# bttoken.net
KiCad netlist of a schematic drawn in EAGLE
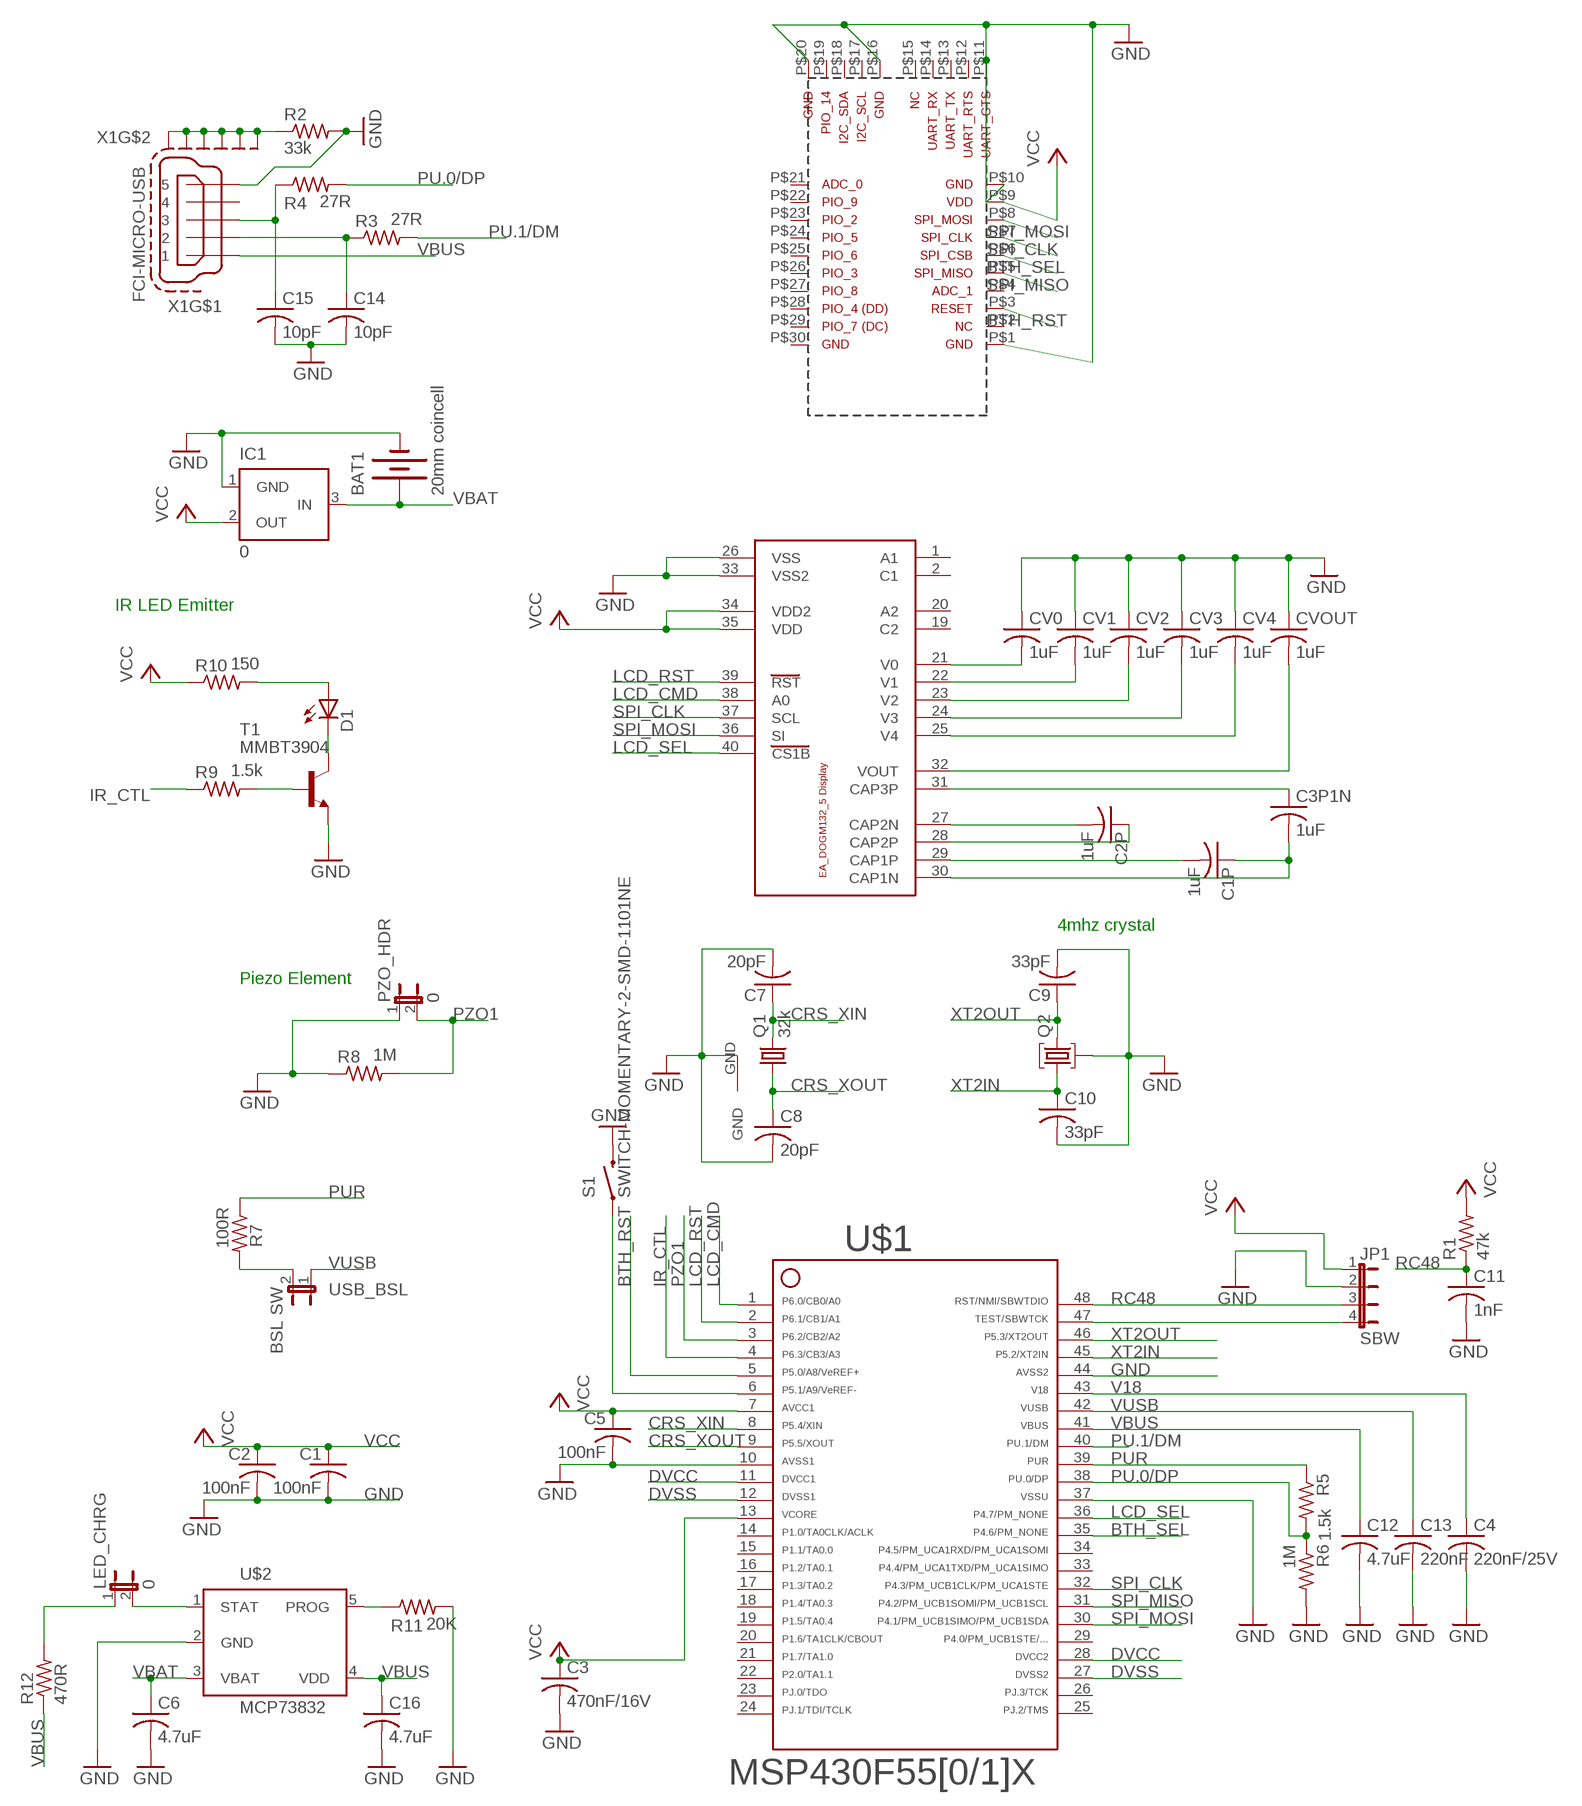
[diagram p0: schematic, sheet 1]

(export (version "E")
  (design (tool "Eeschema 10.0.6"))
  (components
    (comp (ref "BAT1")
      (value "20mm coincell")
      (footprint "eagle-import:BAT-HLD-001")
      (libsource (lib "eagle-import") (part "BAT-HLD-001"))
    )
    (comp (ref "C1")
      (value "100nF")
      (footprint "eagle-import:C0805")
      (libsource (lib "eagle-import") (part "C-USC0805"))
    )
    (comp (ref "C1P")
      (value "1uF")
      (footprint "eagle-import:C0805")
      (libsource (lib "eagle-import") (part "C-USC0805"))
    )
    (comp (ref "C2")
      (value "100nF")
      (footprint "eagle-import:C0805")
      (libsource (lib "eagle-import") (part "C-USC0805"))
    )
    (comp (ref "C2P")
      (value "1uF")
      (footprint "eagle-import:C0805")
      (libsource (lib "eagle-import") (part "C-USC0805"))
    )
    (comp (ref "C3")
      (value "470nF/16V")
      (footprint "eagle-import:C0805")
      (libsource (lib "eagle-import") (part "C-USC0805"))
    )
    (comp (ref "C3P1N")
      (value "1uF")
      (footprint "eagle-import:C0805")
      (libsource (lib "eagle-import") (part "C-USC0805"))
    )
    (comp (ref "C4")
      (value "220nF/25V")
      (footprint "eagle-import:C0805")
      (libsource (lib "eagle-import") (part "C-USC0805"))
    )
    (comp (ref "C5")
      (value "100nF")
      (footprint "eagle-import:C0805")
      (libsource (lib "eagle-import") (part "C-USC0805"))
    )
    (comp (ref "C6")
      (value "4.7uF")
      (footprint "eagle-import:C0805")
      (libsource (lib "eagle-import") (part "C-USC0805"))
    )
    (comp (ref "C7")
      (value "20pF")
      (footprint "eagle-import:C0805")
      (libsource (lib "eagle-import") (part "C-USC0805"))
    )
    (comp (ref "C8")
      (value "20pF")
      (footprint "eagle-import:C0805")
      (libsource (lib "eagle-import") (part "C-USC0805"))
    )
    (comp (ref "C9")
      (value "33pF")
      (footprint "eagle-import:C0805")
      (libsource (lib "eagle-import") (part "C-USC0805"))
    )
    (comp (ref "C10")
      (value "33pF")
      (footprint "eagle-import:C0805")
      (libsource (lib "eagle-import") (part "C-USC0805"))
    )
    (comp (ref "C11")
      (value "1nF")
      (footprint "eagle-import:C0805")
      (libsource (lib "eagle-import") (part "C-USC0805"))
    )
    (comp (ref "C12")
      (value "4.7uF")
      (footprint "eagle-import:C0805")
      (libsource (lib "eagle-import") (part "C-USC0805"))
    )
    (comp (ref "C13")
      (value "220nF")
      (footprint "eagle-import:C0805")
      (libsource (lib "eagle-import") (part "C-USC0805"))
    )
    (comp (ref "C14")
      (value "10pF")
      (footprint "eagle-import:C0805")
      (libsource (lib "eagle-import") (part "C-USC0805"))
    )
    (comp (ref "C15")
      (value "10pF")
      (footprint "eagle-import:C0805")
      (libsource (lib "eagle-import") (part "C-USC0805"))
    )
    (comp (ref "C16")
      (value "4.7uF")
      (footprint "eagle-import:C0805")
      (libsource (lib "eagle-import") (part "C-USC0805"))
    )
    (comp (ref "CV0")
      (value "1uF")
      (footprint "eagle-import:C0805")
      (libsource (lib "eagle-import") (part "C-USC0805"))
    )
    (comp (ref "CV1")
      (value "1uF")
      (footprint "eagle-import:C0805")
      (libsource (lib "eagle-import") (part "C-USC0805"))
    )
    (comp (ref "CV2")
      (value "1uF")
      (footprint "eagle-import:C0805")
      (libsource (lib "eagle-import") (part "C-USC0805"))
    )
    (comp (ref "CV3")
      (value "1uF")
      (footprint "eagle-import:C0805")
      (libsource (lib "eagle-import") (part "C-USC0805"))
    )
    (comp (ref "CV4")
      (value "1uF")
      (footprint "eagle-import:C0805")
      (libsource (lib "eagle-import") (part "C-USC0805"))
    )
    (comp (ref "CVOUT")
      (value "1uF")
      (footprint "eagle-import:C0805")
      (libsource (lib "eagle-import") (part "C-USC0805"))
    )
    (comp (ref "D1")
      (value "SFH482")
      (footprint "eagle-import:SFH482")
      (libsource (lib "eagle-import") (part "SFH482"))
    )
    (comp (ref "IC1")
      (value "0")
      (footprint "eagle-import:SOT23")
      (libsource (lib "eagle-import") (part "MCP1700"))
    )
    (comp (ref "JP1")
      (value "SBW")
      (footprint "eagle-import:JP4")
      (libsource (lib "eagle-import") (part "JMP4E"))
    )
    (comp (ref "LED_CHRG")
      (value "0")
      (footprint "eagle-import:JP1")
      (libsource (lib "eagle-import") (part "JP1E"))
    )
    (comp (ref "PZO_HDR")
      (value "0")
      (footprint "eagle-import:JP1")
      (libsource (lib "eagle-import") (part "JP1E"))
    )
    (comp (ref "Q1")
      (value "32k")
      (footprint "eagle-import:TC26H-SMT")
      (libsource (lib "eagle-import") (part "TC47H-SMT"))
    )
    (comp (ref "Q2")
      (value "10G7A-12.5KHZ")
      (footprint "eagle-import:HC49U")
      (libsource (lib "eagle-import") (part "10G7A-12.5KHZ"))
    )
    (comp (ref "R1")
      (value "47k")
      (footprint "eagle-import:R0805")
      (libsource (lib "eagle-import") (part "R-US_R0805"))
    )
    (comp (ref "R2")
      (value "33k")
      (footprint "eagle-import:R0805")
      (libsource (lib "eagle-import") (part "R-US_R0805"))
    )
    (comp (ref "R3")
      (value "27R")
      (footprint "eagle-import:R0805")
      (libsource (lib "eagle-import") (part "R-US_R0805"))
    )
    (comp (ref "R4")
      (value "27R")
      (footprint "eagle-import:R0805")
      (libsource (lib "eagle-import") (part "R-US_R0805"))
    )
    (comp (ref "R5")
      (value "1.5k")
      (footprint "eagle-import:R0805")
      (libsource (lib "eagle-import") (part "R-US_R0805"))
    )
    (comp (ref "R6")
      (value "1M")
      (footprint "eagle-import:R0805")
      (libsource (lib "eagle-import") (part "R-US_R0805"))
    )
    (comp (ref "R7")
      (value "100R")
      (footprint "eagle-import:R0805")
      (libsource (lib "eagle-import") (part "R-US_R0805"))
    )
    (comp (ref "R8")
      (value "1M")
      (footprint "eagle-import:R0805")
      (libsource (lib "eagle-import") (part "R-US_R0805"))
    )
    (comp (ref "R9")
      (value "1.5k")
      (footprint "eagle-import:R0805")
      (libsource (lib "eagle-import") (part "R-US_R0805"))
    )
    (comp (ref "R10")
      (value "150")
      (footprint "eagle-import:R0805")
      (libsource (lib "eagle-import") (part "R-US_R0805"))
    )
    (comp (ref "R11")
      (value "20K")
      (footprint "eagle-import:R0805")
      (libsource (lib "eagle-import") (part "R-US_R0805"))
    )
    (comp (ref "R12")
      (value "470R")
      (footprint "eagle-import:R0805")
      (libsource (lib "eagle-import") (part "R-US_R0805"))
    )
    (comp (ref "S1")
      (value "SWITCH-MOMENTARY-2-SMD-1101NE")
      (footprint "eagle-import:TACTILE-SWITCH-1101NE")
      (libsource (lib "eagle-import") (part "SWITCH-MOMENTARY-2-SMD-1101NE"))
    )
    (comp (ref "T1")
      (value "MMBT3904")
      (footprint "eagle-import:SOT23-BEC")
      (libsource (lib "eagle-import") (part "-NPN-SOT23-BECMMBT3904LT1"))
    )
    (comp (ref "U$1")
      (value "F55[0/1]X---PT48")
      (footprint "eagle-import:PT48")
      (libsource (lib "eagle-import") (part "F55[0/1]X---PT48"))
    )
    (comp (ref "U$2")
      (value "MCP73832")
      (footprint "eagle-import:SOT23-5")
      (libsource (lib "eagle-import") (part "MCP73832"))
    )
    (comp (ref "U$11")
      (value "DISPLAY_EA_DOGM132_EA_DOG-M_DISPLAY")
      (footprint "eagle-import:DISPLAY_EA_DOGM132_E_DOG-M_DISPLAY")
      (libsource (lib "eagle-import") (part "DISPLAY_EA_DOGM132_EA_DOG-M_DISPLAY"))
    )
    (comp (ref "U$13")
      (value "BR-LE4.0-S3-NC")
      (footprint "eagle-import:BR-LE4.0-X2A-NC")
      (libsource (lib "eagle-import") (part "BR-LE4.0-S3-NC"))
    )
    (comp (ref "USB_BSL")
      (value "BSL SW")
      (footprint "eagle-import:JP1")
      (libsource (lib "eagle-import") (part "JP1E"))
    )
    (comp (ref "X1")
      (value "FCI-MICRO-USB")
      (footprint "eagle-import:FCI-MICRO-USB5")
      (libsource (lib "eagle-import") (part "FCI-MICRO-USB"))
    )
  )
  (nets
    (net (code "1") (name "/BTH_RST") (class "Default")
      (node (ref "U$1") (pin "5") (pinfunction "5_5") (pintype "bidirectional"))
      (node (ref "U$13") (pin "P$3") (pinfunction "P$3_P$3") (pintype "bidirectional"))
    )
    (net (code "2") (name "/BTH_SEL") (class "Default")
      (node (ref "U$1") (pin "35") (pinfunction "35_35") (pintype "bidirectional"))
      (node (ref "U$13") (pin "P$6") (pinfunction "P$6_P$6") (pintype "bidirectional"))
    )
    (net (code "3") (name "/CRS_XIN") (class "Default")
      (node (ref "C7") (pin "1") (pinfunction "1_1") (pintype "passive"))
      (node (ref "Q1") (pin "2") (pinfunction "2_2") (pintype "passive"))
      (node (ref "U$1") (pin "8") (pinfunction "8_8") (pintype "bidirectional"))
    )
    (net (code "4") (name "/CRS_XOUT") (class "Default")
      (node (ref "C8") (pin "1") (pinfunction "1_1") (pintype "passive"))
      (node (ref "Q1") (pin "1") (pinfunction "1_1") (pintype "passive"))
      (node (ref "U$1") (pin "9") (pinfunction "9_9") (pintype "bidirectional"))
    )
    (net (code "5") (name "/DVCC") (class "Default")
      (node (ref "U$1") (pin "11") (pinfunction "11_11") (pintype "power_in"))
      (node (ref "U$1") (pin "28") (pinfunction "28_28") (pintype "power_in"))
    )
    (net (code "6") (name "/DVSS") (class "Default")
      (node (ref "U$1") (pin "12") (pinfunction "12_12") (pintype "power_in"))
      (node (ref "U$1") (pin "27") (pinfunction "27_27") (pintype "power_in"))
    )
    (net (code "7") (name "/IR_CTL") (class "Default")
      (node (ref "R9") (pin "1") (pinfunction "1_1") (pintype "passive"))
      (node (ref "U$1") (pin "4") (pinfunction "4_4") (pintype "bidirectional"))
    )
    (net (code "8") (name "/LCD_CMD") (class "Default")
      (node (ref "U$1") (pin "1") (pinfunction "1_1") (pintype "bidirectional"))
      (node (ref "U$11") (pin "38") (pinfunction "A0_38") (pintype "bidirectional"))
    )
    (net (code "9") (name "/LCD_RST") (class "Default")
      (node (ref "U$1") (pin "2") (pinfunction "2_2") (pintype "bidirectional"))
      (node (ref "U$11") (pin "39") (pinfunction "RST_39") (pintype "bidirectional"))
    )
    (net (code "10") (name "/LCD_SEL") (class "Default")
      (node (ref "U$1") (pin "36") (pinfunction "36_36") (pintype "bidirectional"))
      (node (ref "U$11") (pin "40") (pinfunction "CS1B_40") (pintype "bidirectional"))
    )
    (net (code "11") (name "/PU.0{slash}DP") (class "Default")
      (node (ref "R4") (pin "2") (pinfunction "2_2") (pintype "passive"))
      (node (ref "R5") (pin "2") (pinfunction "2_2") (pintype "passive"))
      (node (ref "R6") (pin "1") (pinfunction "1_1") (pintype "passive"))
      (node (ref "U$1") (pin "38") (pinfunction "38_38") (pintype "bidirectional"))
    )
    (net (code "12") (name "/PU.1{slash}DM") (class "Default")
      (node (ref "R3") (pin "2") (pinfunction "2_2") (pintype "passive"))
      (node (ref "U$1") (pin "40") (pinfunction "40_40") (pintype "bidirectional"))
    )
    (net (code "13") (name "/PUR") (class "Default")
      (node (ref "R5") (pin "1") (pinfunction "1_1") (pintype "passive"))
      (node (ref "R7") (pin "1") (pinfunction "1_1") (pintype "passive"))
      (node (ref "U$1") (pin "39") (pinfunction "39_39") (pintype "bidirectional"))
    )
    (net (code "14") (name "/PZO1") (class "Default")
      (node (ref "PZO_HDR") (pin "2") (pinfunction "2_2") (pintype "passive"))
      (node (ref "R8") (pin "2") (pinfunction "2_2") (pintype "passive"))
      (node (ref "U$1") (pin "3") (pinfunction "3_3") (pintype "bidirectional"))
    )
    (net (code "15") (name "/RC48") (class "Default")
      (node (ref "C11") (pin "1") (pinfunction "1_1") (pintype "passive"))
      (node (ref "JP1") (pin "3") (pinfunction "3_3") (pintype "passive"))
      (node (ref "R1") (pin "1") (pinfunction "1_1") (pintype "passive"))
      (node (ref "U$1") (pin "48") (pinfunction "48_48") (pintype "bidirectional"))
    )
    (net (code "16") (name "/SPI_CLK") (class "Default")
      (node (ref "U$1") (pin "32") (pinfunction "32_32") (pintype "bidirectional"))
      (node (ref "U$11") (pin "37") (pinfunction "SCL_37") (pintype "bidirectional"))
      (node (ref "U$13") (pin "P$7") (pinfunction "P$7_P$7") (pintype "bidirectional"))
    )
    (net (code "17") (name "/SPI_MISO") (class "Default")
      (node (ref "U$1") (pin "31") (pinfunction "31_31") (pintype "bidirectional"))
      (node (ref "U$13") (pin "P$5") (pinfunction "P$5_P$5") (pintype "bidirectional"))
    )
    (net (code "18") (name "/SPI_MOSI") (class "Default")
      (node (ref "U$1") (pin "30") (pinfunction "30_30") (pintype "bidirectional"))
      (node (ref "U$11") (pin "36") (pinfunction "SI_36") (pintype "bidirectional"))
      (node (ref "U$13") (pin "P$8") (pinfunction "P$8_P$8") (pintype "bidirectional"))
    )
    (net (code "19") (name "/V18") (class "Default")
      (node (ref "C4") (pin "1") (pinfunction "1_1") (pintype "passive"))
      (node (ref "U$1") (pin "43") (pinfunction "43_43") (pintype "power_in"))
    )
    (net (code "20") (name "/VBAT") (class "Default")
      (node (ref "BAT1") (pin "P$2+") (pinfunction "+_P$2+") (pintype "power_in"))
      (node (ref "BAT1") (pin "P$3+") (pinfunction "+_P$3+") (pintype "power_in"))
      (node (ref "C6") (pin "1") (pinfunction "1_1") (pintype "passive"))
      (node (ref "IC1") (pin "3") (pinfunction "IN_3") (pintype "input"))
      (node (ref "U$2") (pin "3") (pinfunction "VBAT_3") (pintype "input"))
    )
    (net (code "21") (name "/VBUS") (class "Default")
      (node (ref "C12") (pin "1") (pinfunction "1_1") (pintype "passive"))
      (node (ref "C16") (pin "1") (pinfunction "1_1") (pintype "passive"))
      (node (ref "R12") (pin "1") (pinfunction "1_1") (pintype "passive"))
      (node (ref "U$1") (pin "41") (pinfunction "41_41") (pintype "power_in"))
      (node (ref "U$2") (pin "4") (pinfunction "VDD_4") (pintype "input"))
      (node (ref "X1") (pin "1") (pinfunction "1_1") (pintype "passive"))
    )
    (net (code "22") (name "/VUSB") (class "Default")
      (node (ref "C13") (pin "1") (pinfunction "1_1") (pintype "passive"))
      (node (ref "U$1") (pin "42") (pinfunction "42_42") (pintype "power_in"))
      (node (ref "USB_BSL") (pin "1") (pinfunction "1_1") (pintype "passive"))
    )
    (net (code "23") (name "/XT2IN") (class "Default")
      (node (ref "C10") (pin "1") (pinfunction "1_1") (pintype "passive"))
      (node (ref "Q2") (pin "1") (pinfunction "1_1") (pintype "passive"))
      (node (ref "U$1") (pin "45") (pinfunction "45_45") (pintype "bidirectional"))
    )
    (net (code "24") (name "/XT2OUT") (class "Default")
      (node (ref "C9") (pin "1") (pinfunction "1_1") (pintype "passive"))
      (node (ref "Q2") (pin "3") (pinfunction "3_3") (pintype "passive"))
      (node (ref "U$1") (pin "46") (pinfunction "46_46") (pintype "power_in"))
    )
    (net (code "25") (name "GND") (class "Default")
      (node (ref "BAT1") (pin "P$1-") (pinfunction "-_P$1-") (pintype "power_in"))
      (node (ref "C1") (pin "2") (pinfunction "2_2") (pintype "passive"))
      (node (ref "C10") (pin "2") (pinfunction "2_2") (pintype "passive"))
      (node (ref "C11") (pin "2") (pinfunction "2_2") (pintype "passive"))
      (node (ref "C12") (pin "2") (pinfunction "2_2") (pintype "passive"))
      (node (ref "C13") (pin "2") (pinfunction "2_2") (pintype "passive"))
      (node (ref "C14") (pin "2") (pinfunction "2_2") (pintype "passive"))
      (node (ref "C15") (pin "2") (pinfunction "2_2") (pintype "passive"))
      (node (ref "C16") (pin "2") (pinfunction "2_2") (pintype "passive"))
      (node (ref "C2") (pin "2") (pinfunction "2_2") (pintype "passive"))
      (node (ref "C3") (pin "2") (pinfunction "2_2") (pintype "passive"))
      (node (ref "C4") (pin "2") (pinfunction "2_2") (pintype "passive"))
      (node (ref "C5") (pin "2") (pinfunction "2_2") (pintype "passive"))
      (node (ref "C6") (pin "2") (pinfunction "2_2") (pintype "passive"))
      (node (ref "C7") (pin "2") (pinfunction "2_2") (pintype "passive"))
      (node (ref "C8") (pin "2") (pinfunction "2_2") (pintype "passive"))
      (node (ref "C9") (pin "2") (pinfunction "2_2") (pintype "passive"))
      (node (ref "CV0") (pin "1") (pinfunction "1_1") (pintype "passive"))
      (node (ref "CV1") (pin "1") (pinfunction "1_1") (pintype "passive"))
      (node (ref "CV2") (pin "1") (pinfunction "1_1") (pintype "passive"))
      (node (ref "CV3") (pin "1") (pinfunction "1_1") (pintype "passive"))
      (node (ref "CV4") (pin "1") (pinfunction "1_1") (pintype "passive"))
      (node (ref "CVOUT") (pin "1") (pinfunction "1_1") (pintype "passive"))
      (node (ref "IC1") (pin "1") (pinfunction "GND_1") (pintype "power_in"))
      (node (ref "JP1") (pin "2") (pinfunction "2_2") (pintype "passive"))
      (node (ref "PZO_HDR") (pin "1") (pinfunction "1_1") (pintype "passive"))
      (node (ref "Q1") (pin "GND") (pinfunction "GND_GND") (pintype "bidirectional"))
      (node (ref "Q2") (pin "2") (pinfunction "2_2") (pintype "passive"))
      (node (ref "R11") (pin "2") (pinfunction "2_2") (pintype "passive"))
      (node (ref "R2") (pin "2") (pinfunction "2_2") (pintype "passive"))
      (node (ref "R6") (pin "2") (pinfunction "2_2") (pintype "passive"))
      (node (ref "R8") (pin "1") (pinfunction "1_1") (pintype "passive"))
      (node (ref "S1") (pin "P$2") (pinfunction "2_P$2") (pintype "passive"))
      (node (ref "T1") (pin "E") (pinfunction "E_E") (pintype "passive"))
      (node (ref "U$1") (pin "10") (pinfunction "10_10") (pintype "power_in"))
      (node (ref "U$1") (pin "37") (pinfunction "37_37") (pintype "power_in"))
      (node (ref "U$1") (pin "44") (pinfunction "44_44") (pintype "power_in"))
      (node (ref "U$11") (pin "26") (pinfunction "VSS_26") (pintype "bidirectional"))
      (node (ref "U$11") (pin "33") (pinfunction "VSS2_33") (pintype "bidirectional"))
      (node (ref "U$13") (pin "P$1") (pinfunction "P$1_P$1") (pintype "bidirectional"))
      (node (ref "U$13") (pin "P$10") (pinfunction "P$10_P$10") (pintype "bidirectional"))
      (node (ref "U$13") (pin "P$11") (pinfunction "P$11_P$11") (pintype "bidirectional"))
      (node (ref "U$13") (pin "P$16") (pinfunction "P$16_P$16") (pintype "bidirectional"))
      (node (ref "U$13") (pin "P$20") (pinfunction "P$20_P$20") (pintype "bidirectional"))
      (node (ref "U$2") (pin "2") (pinfunction "GND_2") (pintype "power_in"))
      (node (ref "X1") (pin "5") (pinfunction "5_5") (pintype "passive"))
    )
    (net (code "26") (name "Net-(C14-Pad1)") (class "Default")
      (node (ref "C14") (pin "1") (pinfunction "1_1") (pintype "passive"))
      (node (ref "R3") (pin "1") (pinfunction "1_1") (pintype "passive"))
      (node (ref "X1") (pin "2") (pinfunction "2_2") (pintype "passive"))
    )
    (net (code "27") (name "Net-(C15-Pad1)") (class "Default")
      (node (ref "C15") (pin "1") (pinfunction "1_1") (pintype "passive"))
      (node (ref "R4") (pin "1") (pinfunction "1_1") (pintype "passive"))
      (node (ref "X1") (pin "3") (pinfunction "3_3") (pintype "passive"))
    )
    (net (code "28") (name "Net-(D1-C)") (class "Default")
      (node (ref "D1") (pin "K") (pinfunction "C_K") (pintype "passive"))
      (node (ref "T1") (pin "C") (pinfunction "C_C") (pintype "passive"))
    )
    (net (code "29") (name "Net-(D1-PadA)") (class "Default")
      (node (ref "D1") (pin "A") (pinfunction "A_A") (pintype "passive"))
      (node (ref "R10") (pin "2") (pinfunction "2_2") (pintype "passive"))
    )
    (net (code "30") (name "Net-(JP1-Pad4)") (class "Default")
      (node (ref "JP1") (pin "4") (pinfunction "4_4") (pintype "passive"))
      (node (ref "U$1") (pin "47") (pinfunction "47_47") (pintype "input"))
    )
    (net (code "31") (name "Net-(LED_CHRG-Pad1)") (class "Default")
      (node (ref "LED_CHRG") (pin "1") (pinfunction "1_1") (pintype "passive"))
      (node (ref "R12") (pin "2") (pinfunction "2_2") (pintype "passive"))
    )
    (net (code "32") (name "Net-(R7-Pad2)") (class "Default")
      (node (ref "R7") (pin "2") (pinfunction "2_2") (pintype "passive"))
      (node (ref "USB_BSL") (pin "2") (pinfunction "2_2") (pintype "passive"))
    )
    (net (code "33") (name "Net-(R9-Pad2)") (class "Default")
      (node (ref "R9") (pin "2") (pinfunction "2_2") (pintype "passive"))
      (node (ref "T1") (pin "B") (pinfunction "B_B") (pintype "passive"))
    )
    (net (code "34") (name "Net-(S1-1)") (class "Default")
      (node (ref "S1") (pin "P$1") (pinfunction "1_P$1") (pintype "passive"))
      (node (ref "U$1") (pin "6") (pinfunction "6_6") (pintype "bidirectional"))
    )
    (net (code "35") (name "Net-(U$2-PROG)") (class "Default")
      (node (ref "R11") (pin "1") (pinfunction "1_1") (pintype "passive"))
      (node (ref "U$2") (pin "5") (pinfunction "PROG_5") (pintype "input"))
    )
    (net (code "36") (name "Net-(U$2-STAT)") (class "Default")
      (node (ref "LED_CHRG") (pin "2") (pinfunction "2_2") (pintype "passive"))
      (node (ref "U$2") (pin "1") (pinfunction "STAT_1") (pintype "input"))
    )
    (net (code "37") (name "Net-(U$11-CAP1N)") (class "Default")
      (node (ref "C1P") (pin "1") (pinfunction "1_1") (pintype "passive"))
      (node (ref "C3P1N") (pin "2") (pinfunction "2_2") (pintype "passive"))
      (node (ref "U$11") (pin "30") (pinfunction "CAP1N_30") (pintype "bidirectional"))
    )
    (net (code "38") (name "Net-(U$11-CAP1P)") (class "Default")
      (node (ref "C1P") (pin "2") (pinfunction "2_2") (pintype "passive"))
      (node (ref "U$11") (pin "29") (pinfunction "CAP1P_29") (pintype "bidirectional"))
    )
    (net (code "39") (name "Net-(U$11-CAP2N)") (class "Default")
      (node (ref "C2P") (pin "2") (pinfunction "2_2") (pintype "passive"))
      (node (ref "U$11") (pin "27") (pinfunction "CAP2N_27") (pintype "bidirectional"))
    )
    (net (code "40") (name "Net-(U$11-CAP2P)") (class "Default")
      (node (ref "C2P") (pin "1") (pinfunction "1_1") (pintype "passive"))
      (node (ref "U$11") (pin "28") (pinfunction "CAP2P_28") (pintype "bidirectional"))
    )
    (net (code "41") (name "Net-(U$11-CAP3P)") (class "Default")
      (node (ref "C3P1N") (pin "1") (pinfunction "1_1") (pintype "passive"))
      (node (ref "U$11") (pin "31") (pinfunction "CAP3P_31") (pintype "bidirectional"))
    )
    (net (code "42") (name "Net-(U$11-V0)") (class "Default")
      (node (ref "CV0") (pin "2") (pinfunction "2_2") (pintype "passive"))
      (node (ref "U$11") (pin "21") (pinfunction "V0_21") (pintype "power_in"))
    )
    (net (code "43") (name "Net-(U$11-V1)") (class "Default")
      (node (ref "CV1") (pin "2") (pinfunction "2_2") (pintype "passive"))
      (node (ref "U$11") (pin "22") (pinfunction "V1_22") (pintype "power_in"))
    )
    (net (code "44") (name "Net-(U$11-V2)") (class "Default")
      (node (ref "CV2") (pin "2") (pinfunction "2_2") (pintype "passive"))
      (node (ref "U$11") (pin "23") (pinfunction "V2_23") (pintype "bidirectional"))
    )
    (net (code "45") (name "Net-(U$11-V3)") (class "Default")
      (node (ref "CV3") (pin "2") (pinfunction "2_2") (pintype "passive"))
      (node (ref "U$11") (pin "24") (pinfunction "V3_24") (pintype "bidirectional"))
    )
    (net (code "46") (name "Net-(U$11-V4)") (class "Default")
      (node (ref "CV4") (pin "2") (pinfunction "2_2") (pintype "passive"))
      (node (ref "U$11") (pin "25") (pinfunction "V4_25") (pintype "bidirectional"))
    )
    (net (code "47") (name "Net-(U$11-VOUT)") (class "Default")
      (node (ref "CVOUT") (pin "2") (pinfunction "2_2") (pintype "passive"))
      (node (ref "U$11") (pin "32") (pinfunction "VOUT_32") (pintype "bidirectional"))
    )
    (net (code "48") (name "Net-(X1B-S1)") (class "Default")
      (node (ref "R2") (pin "1") (pinfunction "1_1") (pintype "passive"))
      (node (ref "X1") (pin "M1") (pinfunction "S1_M1") (pintype "passive"))
      (node (ref "X1") (pin "M2") (pinfunction "S2_M2") (pintype "passive"))
      (node (ref "X1") (pin "M3") (pinfunction "S3_M3") (pintype "passive"))
      (node (ref "X1") (pin "M4") (pinfunction "S4_M4") (pintype "passive"))
      (node (ref "X1") (pin "M5") (pinfunction "S5_M5") (pintype "passive"))
      (node (ref "X1") (pin "M6") (pinfunction "S6_M6") (pintype "passive"))
    )
    (net (code "49") (name "VCC") (class "Default")
      (node (ref "C1") (pin "1") (pinfunction "1_1") (pintype "passive"))
      (node (ref "C2") (pin "1") (pinfunction "1_1") (pintype "passive"))
      (node (ref "C3") (pin "1") (pinfunction "1_1") (pintype "passive"))
      (node (ref "C5") (pin "1") (pinfunction "1_1") (pintype "passive"))
      (node (ref "IC1") (pin "2") (pinfunction "OUT_2") (pintype "input"))
      (node (ref "JP1") (pin "1") (pinfunction "1_1") (pintype "passive"))
      (node (ref "R1") (pin "2") (pinfunction "2_2") (pintype "passive"))
      (node (ref "R10") (pin "1") (pinfunction "1_1") (pintype "passive"))
      (node (ref "U$1") (pin "13") (pinfunction "13_13") (pintype "power_in"))
      (node (ref "U$1") (pin "7") (pinfunction "7_7") (pintype "power_in"))
      (node (ref "U$11") (pin "34") (pinfunction "VDD2_34") (pintype "bidirectional"))
      (node (ref "U$11") (pin "35") (pinfunction "VDD_35") (pintype "bidirectional"))
      (node (ref "U$13") (pin "P$9") (pinfunction "P$9_P$9") (pintype "bidirectional"))
    )
    (net (code "50") (name "unconnected-(U$1-Pad14)") (class "Default")
      (node (ref "U$1") (pin "14") (pinfunction "14_14") (pintype "bidirectional"))
    )
    (net (code "51") (name "unconnected-(U$1-Pad15)") (class "Default")
      (node (ref "U$1") (pin "15") (pinfunction "15_15") (pintype "bidirectional"))
    )
    (net (code "52") (name "unconnected-(U$1-Pad16)") (class "Default")
      (node (ref "U$1") (pin "16") (pinfunction "16_16") (pintype "bidirectional"))
    )
    (net (code "53") (name "unconnected-(U$1-Pad17)") (class "Default")
      (node (ref "U$1") (pin "17") (pinfunction "17_17") (pintype "bidirectional"))
    )
    (net (code "54") (name "unconnected-(U$1-Pad18)") (class "Default")
      (node (ref "U$1") (pin "18") (pinfunction "18_18") (pintype "bidirectional"))
    )
    (net (code "55") (name "unconnected-(U$1-Pad19)") (class "Default")
      (node (ref "U$1") (pin "19") (pinfunction "19_19") (pintype "bidirectional"))
    )
    (net (code "56") (name "unconnected-(U$1-Pad20)") (class "Default")
      (node (ref "U$1") (pin "20") (pinfunction "20_20") (pintype "bidirectional"))
    )
    (net (code "57") (name "unconnected-(U$1-Pad21)") (class "Default")
      (node (ref "U$1") (pin "21") (pinfunction "21_21") (pintype "bidirectional"))
    )
    (net (code "58") (name "unconnected-(U$1-Pad22)") (class "Default")
      (node (ref "U$1") (pin "22") (pinfunction "22_22") (pintype "bidirectional"))
    )
    (net (code "59") (name "unconnected-(U$1-Pad23)") (class "Default")
      (node (ref "U$1") (pin "23") (pinfunction "23_23") (pintype "bidirectional"))
    )
    (net (code "60") (name "unconnected-(U$1-Pad24)") (class "Default")
      (node (ref "U$1") (pin "24") (pinfunction "24_24") (pintype "bidirectional"))
    )
    (net (code "61") (name "unconnected-(U$1-Pad25)") (class "Default")
      (node (ref "U$1") (pin "25") (pinfunction "25_25") (pintype "bidirectional"))
    )
    (net (code "62") (name "unconnected-(U$1-Pad26)") (class "Default")
      (node (ref "U$1") (pin "26") (pinfunction "26_26") (pintype "bidirectional"))
    )
    (net (code "63") (name "unconnected-(U$1-Pad29)") (class "Default")
      (node (ref "U$1") (pin "29") (pinfunction "29_29") (pintype "bidirectional"))
    )
    (net (code "64") (name "unconnected-(U$1-Pad33)") (class "Default")
      (node (ref "U$1") (pin "33") (pinfunction "33_33") (pintype "bidirectional"))
    )
    (net (code "65") (name "unconnected-(U$1-Pad34)") (class "Default")
      (node (ref "U$1") (pin "34") (pinfunction "34_34") (pintype "bidirectional"))
    )
    (net (code "66") (name "unconnected-(U$11-A1-Pad1)") (class "Default")
      (node (ref "U$11") (pin "1") (pinfunction "A1_1") (pintype "bidirectional"))
    )
    (net (code "67") (name "unconnected-(U$11-A2-Pad20)") (class "Default")
      (node (ref "U$11") (pin "20") (pinfunction "A2_20") (pintype "bidirectional"))
    )
    (net (code "68") (name "unconnected-(U$11-C1-Pad2)") (class "Default")
      (node (ref "U$11") (pin "2") (pinfunction "C1_2") (pintype "bidirectional"))
    )
    (net (code "69") (name "unconnected-(U$11-C2-Pad19)") (class "Default")
      (node (ref "U$11") (pin "19") (pinfunction "C2_19") (pintype "bidirectional"))
    )
    (net (code "70") (name "unconnected-(U$13-PadP$2)") (class "Default")
      (node (ref "U$13") (pin "P$2") (pinfunction "P$2_P$2") (pintype "no_connect"))
    )
    (net (code "71") (name "unconnected-(U$13-PadP$4)") (class "Default")
      (node (ref "U$13") (pin "P$4") (pinfunction "P$4_P$4") (pintype "bidirectional"))
    )
    (net (code "72") (name "unconnected-(U$13-PadP$12)") (class "Default")
      (node (ref "U$13") (pin "P$12") (pinfunction "P$12_P$12") (pintype "bidirectional"))
    )
    (net (code "73") (name "unconnected-(U$13-PadP$13)") (class "Default")
      (node (ref "U$13") (pin "P$13") (pinfunction "P$13_P$13") (pintype "bidirectional"))
    )
    (net (code "74") (name "unconnected-(U$13-PadP$14)") (class "Default")
      (node (ref "U$13") (pin "P$14") (pinfunction "P$14_P$14") (pintype "bidirectional"))
    )
    (net (code "75") (name "unconnected-(U$13-PadP$15)") (class "Default")
      (node (ref "U$13") (pin "P$15") (pinfunction "P$15_P$15") (pintype "no_connect"))
    )
    (net (code "76") (name "unconnected-(U$13-PadP$17)") (class "Default")
      (node (ref "U$13") (pin "P$17") (pinfunction "P$17_P$17") (pintype "bidirectional"))
    )
    (net (code "77") (name "unconnected-(U$13-PadP$18)") (class "Default")
      (node (ref "U$13") (pin "P$18") (pinfunction "P$18_P$18") (pintype "bidirectional"))
    )
    (net (code "78") (name "unconnected-(U$13-PadP$19)") (class "Default")
      (node (ref "U$13") (pin "P$19") (pinfunction "P$19_P$19") (pintype "bidirectional"))
    )
    (net (code "79") (name "unconnected-(U$13-PadP$21)") (class "Default")
      (node (ref "U$13") (pin "P$21") (pinfunction "P$21_P$21") (pintype "bidirectional"))
    )
    (net (code "80") (name "unconnected-(U$13-PadP$22)") (class "Default")
      (node (ref "U$13") (pin "P$22") (pinfunction "P$22_P$22") (pintype "bidirectional"))
    )
    (net (code "81") (name "unconnected-(U$13-PadP$23)") (class "Default")
      (node (ref "U$13") (pin "P$23") (pinfunction "P$23_P$23") (pintype "bidirectional"))
    )
    (net (code "82") (name "unconnected-(U$13-PadP$24)") (class "Default")
      (node (ref "U$13") (pin "P$24") (pinfunction "P$24_P$24") (pintype "bidirectional"))
    )
    (net (code "83") (name "unconnected-(U$13-PadP$25)") (class "Default")
      (node (ref "U$13") (pin "P$25") (pinfunction "P$25_P$25") (pintype "bidirectional"))
    )
    (net (code "84") (name "unconnected-(U$13-PadP$26)") (class "Default")
      (node (ref "U$13") (pin "P$26") (pinfunction "P$26_P$26") (pintype "bidirectional"))
    )
    (net (code "85") (name "unconnected-(U$13-PadP$27)") (class "Default")
      (node (ref "U$13") (pin "P$27") (pinfunction "P$27_P$27") (pintype "bidirectional"))
    )
    (net (code "86") (name "unconnected-(U$13-PadP$28)") (class "Default")
      (node (ref "U$13") (pin "P$28") (pinfunction "P$28_P$28") (pintype "bidirectional"))
    )
    (net (code "87") (name "unconnected-(U$13-PadP$29)") (class "Default")
      (node (ref "U$13") (pin "P$29") (pinfunction "P$29_P$29") (pintype "bidirectional"))
    )
    (net (code "88") (name "unconnected-(U$13-PadP$30)") (class "Default")
      (node (ref "U$13") (pin "P$30") (pinfunction "P$30_P$30") (pintype "bidirectional"))
    )
    (net (code "89") (name "unconnected-(X1-Pad4)") (class "Default")
      (node (ref "X1") (pin "4") (pinfunction "4_4") (pintype "passive"))
    )
  )
)
